# USB.net
KiCad netlist of a schematic drawn in Altium Designer
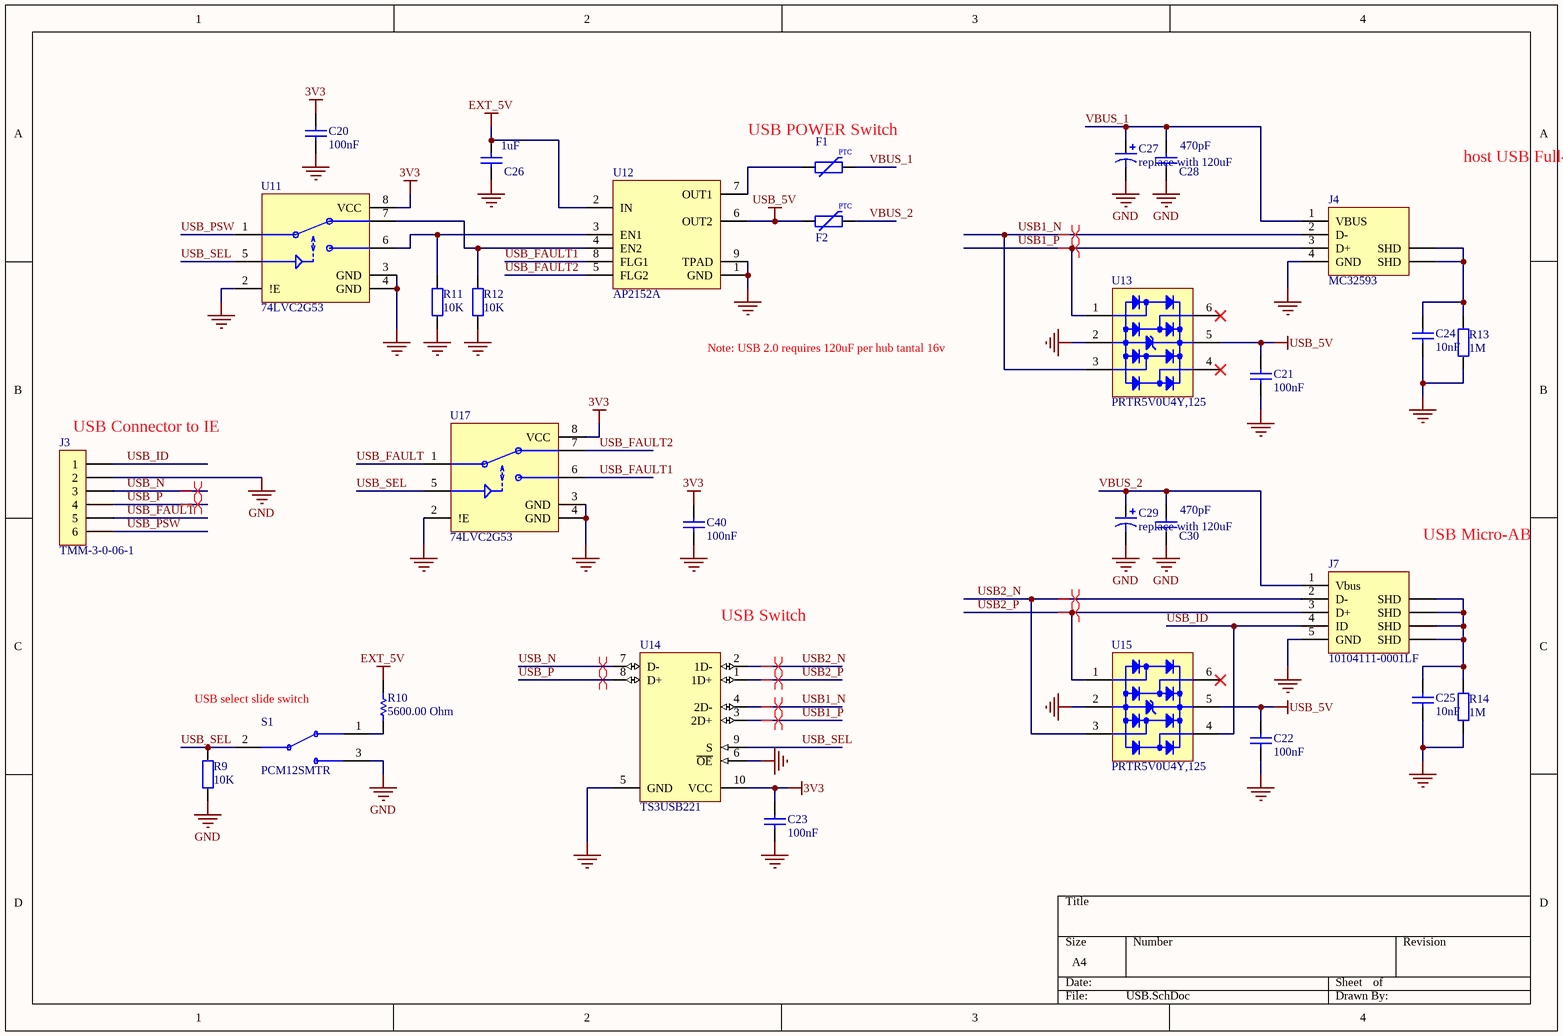
[diagram p0: USB.SchDoc]

(export (version "E")
  (design (tool "Eeschema 10.0.6"))
  (components
    (comp (ref "C20")
      (value "100nF")
      (footprint "CAPC0402(1005)60_L")
      (description "CAP 100nF 10V ±5% 0402 (1005 Metric) Thickness 0.6mm SMD")
      (fields (field (name "TOLERANCE") "Â±5%") (field (name "Comment") "CAP 100nF 10V 0402(1005)"))
      (libsource (lib "Altium Content Vault") (part "CMP-1034-02064-1"))
    )
    (comp (ref "C21")
      (value "100nF")
      (footprint "CAPC0402(1005)60_L")
      (description "CAP 100nF 10V ±5% 0402 (1005 Metric) Thickness 0.6mm SMD")
      (fields (field (name "TOLERANCE") "Â±5%") (field (name "Comment") "CAP 100nF 10V 0402(1005)"))
      (libsource (lib "Altium Content Vault") (part "CMP-1034-02064-1"))
    )
    (comp (ref "C22")
      (value "100nF")
      (footprint "CAPC0402(1005)60_L")
      (description "CAP 100nF 10V ±5% 0402 (1005 Metric) Thickness 0.6mm SMD")
      (fields (field (name "TOLERANCE") "Â±5%") (field (name "Comment") "CAP 100nF 10V 0402(1005)"))
      (libsource (lib "Altium Content Vault") (part "CMP-1034-02064-1"))
    )
    (comp (ref "C23")
      (value "100nF")
      (footprint "CAPC0402(1005)60_L")
      (description "CAP 100nF 10V ±5% 0402 (1005 Metric) Thickness 0.6mm SMD")
      (fields (field (name "TOLERANCE") "Â±5%") (field (name "Comment") "CAP 100nF 10V 0402(1005)"))
      (libsource (lib "Altium Content Vault") (part "CMP-1034-02064-1"))
    )
    (comp (ref "C24")
      (value "10nF")
      (footprint "CAPC0402(1005)60_N")
      (description "CAP 10nF 50V ±10% 0402 (1005 Metric) Thickness 0.6mm SMD")
      (fields (field (name "TOLERANCE") "±10%") (field (name "Comment") "CAP 10nF 50V 0402(1005)"))
      (libsource (lib "Altium Content Vault") (part "CMP-1034-01886-1"))
    )
    (comp (ref "C25")
      (value "10nF")
      (footprint "CAPC0402(1005)60_N")
      (description "CAP 10nF 50V ±10% 0402 (1005 Metric) Thickness 0.6mm SMD")
      (fields (field (name "TOLERANCE") "±10%") (field (name "Comment") "CAP 10nF 50V 0402(1005)"))
      (libsource (lib "Altium Content Vault") (part "CMP-1034-01886-1"))
    )
    (comp (ref "C26")
      (value "1uF")
      (footprint "CAPC0603(1608)100_N")
      (description "CAP 2.2uF 16V ±20% 0603 (1608 Metric) Thickness 1mm SMD")
      (fields (field (name "TOLERANCE") "±20%") (field (name "Comment") "CAP 2.2uF 16V 0603(1608)"))
      (libsource (lib "Altium Content Vault") (part "CMP-1035-02765-1"))
    )
    (comp (ref "C27")
      (value "replace with 120uF")
      (footprint "AVX-CAPC3528_V")
      (description "Capacitor, Tantalum, 10uF 10% 20V MCCT-B (3528)")
      (fields (field (name "PARTNUMBER") "TAJB106K020R") (field (name "MANUFACTURER") "AVX"))
      (libsource (lib "Altium Content Vault") (part "CMP-0279-00001-1"))
    )
    (comp (ref "C28")
      (value "470pF")
      (footprint "CAPC0603(1608)100_M")
      (description "CAP 470pF 16V ±1% 0603 (1608 Metric) Thickness 1mm SMD")
      (fields (field (name "TOLERANCE") "Â±1%") (field (name "Comment") "CAP 470pF 16V 0603(1608)"))
      (libsource (lib "Altium Content Vault") (part "CMP-1035-01663-1"))
    )
    (comp (ref "C29")
      (value "replace with 120uF")
      (footprint "AVX-CAPC3528_V")
      (description "Capacitor, Tantalum, 10uF 10% 20V MCCT-B (3528)")
      (fields (field (name "PARTNUMBER") "TAJB106K020R") (field (name "MANUFACTURER") "AVX"))
      (libsource (lib "Altium Content Vault") (part "CMP-0279-00001-1"))
    )
    (comp (ref "C30")
      (value "470pF")
      (footprint "CAPC0603(1608)100_M")
      (description "CAP 470pF 16V ±1% 0603 (1608 Metric) Thickness 1mm SMD")
      (fields (field (name "TOLERANCE") "Â±1%") (field (name "Comment") "CAP 470pF 16V 0603(1608)"))
      (libsource (lib "Altium Content Vault") (part "CMP-1035-01663-1"))
    )
    (comp (ref "C40")
      (value "100nF")
      (footprint "CAPC0402(1005)60_L")
      (description "CAP 100nF 10V ±5% 0402 (1005 Metric) Thickness 0.6mm SMD")
      (fields (field (name "TOLERANCE") "Â±5%") (field (name "Comment") "CAP 100nF 10V 0402(1005)"))
      (libsource (lib "Altium Content Vault") (part "CMP-1034-02064-1"))
    )
    (comp (ref "F1")
      (value "MF-PSMF050X-2")
      (footprint "RESC0805(2012)_L")
      (description "PTC Resettable Fuse")
      (fields (field (name "MANUFACTURER") "Bourns"))
      (libsource (lib "MF-PSMF050X-2") (part "MF-PSMF050X-2"))
    )
    (comp (ref "F2")
      (value "MF-PSMF050X-2")
      (footprint "RESC0805(2012)_L")
      (description "PTC Resettable Fuse")
      (libsource (lib "MF-PSMF050X-2") (part "MF-PSMF050X-2"))
    )
    (comp (ref "J3")
      (value "TMM-3-0-06-1")
      (footprint "Micro-Match_6pin")
      (description "Micro-Match male 6 pin  Through Hole Vertical, Pitch 1.27mm")
      (fields (field (name "MANUFACTURER") "AMPHENOL"))
      (libsource (lib "TMM-3-0-06-1") (part "TMM-3-0-06-1"))
    )
    (comp (ref "J4")
      (value "MC32593")
      (footprint "MC32593")
      (description "USB, Type A, Right Angle, THT")
      (fields (field (name "MANUFACTURER") "MULTICOMP"))
      (libsource (lib "MC32593") (part "MC32593"))
    )
    (comp (ref "J7")
      (value "10104111-0001LF")
      (footprint "10104111-0001LF")
      (description "Micro USB 2.0, Type AB, Bottom Mount, SMT, Right Angle")
      (libsource (lib "10104111-0001LF") (part "10104111-0001LF"))
    )
    (comp (ref "R9")
      (value "10K")
      (footprint "RESC0402(1005)_L")
      (description "10K 0.063W 1% 0402 (1005 Metric)  SMD")
      (fields (field (name "POWER") "0.063W") (field (name "TOLERANCE") "1%"))
      (libsource (lib "RES0402(1005)") (part "10K 0402(1005)_1"))
    )
    (comp (ref "R10")
      (value "5600.00 Ohm")
      (footprint "RESC0402(1005)_L")
      (description "5K6 0.063W 5% 0402 (1005 Metric)  SMD")
      (fields (field (name "TOLERANCE") "5 %") (field (name "POWER") "0.063 W"))
      (libsource (lib "Altium Content Vault") (part "CMP-1011-00092-1"))
    )
    (comp (ref "R11")
      (value "10K")
      (footprint "RESC0402(1005)_N")
      (description "10K 0.063W 1% 0402 (1005 Metric)  SMD")
      (fields (field (name "POWER") "0.063W") (field (name "TOLERANCE") "1%"))
      (libsource (lib "RES0402(1005)") (part "10K 0402(1005)_1"))
    )
    (comp (ref "R12")
      (value "10K")
      (footprint "RESC0402(1005)_N")
      (description "10K 0.063W 1% 0402 (1005 Metric)  SMD")
      (fields (field (name "POWER") "0.063W") (field (name "TOLERANCE") "1%"))
      (libsource (lib "RES0402(1005)") (part "10K 0402(1005)_1"))
    )
    (comp (ref "R13")
      (value "1M")
      (footprint "RESC0402(1005)_L")
      (description "1M  0.063W 1% 0402 (1005 Metric)  SMD")
      (fields (field (name "POWER") "0.063W") (field (name "TOLERANCE") "1%"))
      (libsource (lib "RES0402(1005)") (part "1M 0402(1005)"))
    )
    (comp (ref "R14")
      (value "1M")
      (footprint "RESC0402(1005)_L")
      (description "1M  0.063W 1% 0402 (1005 Metric)  SMD")
      (fields (field (name "POWER") "0.063W") (field (name "TOLERANCE") "1%"))
      (libsource (lib "RES0402(1005)") (part "1M 0402(1005)"))
    )
    (comp (ref "S1")
      (value "PCM12SMTR")
      (footprint "PCM12SMTR switch footprint")
      (description "slide switch")
      (fields (field (name "MANUFACTURER") "C & K COMPONENTS"))
      (libsource (lib "PCM12SMTR") (part "PCM12SMTR"))
    )
    (comp (ref "U11")
      (value "74LVC2G53")
      (footprint "VSSOP8_SOT765-1")
      (libsource (lib "74LVC2G53") (part "74LVC2G53"))
    )
    (comp (ref "U12")
      (value "AP2152A")
      (footprint "SOP127P600-8N")
      (libsource (lib "AP2152A") (part "AP2152A"))
    )
    (comp (ref "U13")
      (value "PRTR5V0U4Y,125")
      (footprint "SOT363_L")
      (fields (field (name "MANUFACTURER") "NXP"))
      (libsource (lib "PRTR5V0U4Y") (part "PRTR5V0U4Y,125"))
    )
    (comp (ref "U14")
      (value "TS3USB221")
      (footprint "RSE10")
      (fields (field (name "PARTNUMBER") "TS3USB221ARSER") (field (name "MANUFACTURER") "Texas Instruments"))
      (libsource (lib "Altium Content Vault") (part "CMP-0309-00017-1"))
    )
    (comp (ref "U15")
      (value "PRTR5V0U4Y,125")
      (footprint "SOT363_L")
      (fields (field (name "MANUFACTURER") "NXP"))
      (libsource (lib "PRTR5V0U4Y") (part "PRTR5V0U4Y,125"))
    )
    (comp (ref "U17")
      (value "74LVC2G53")
      (footprint "VSSOP8_SOT765-1")
      (libsource (lib "74LVC2G53") (part "74LVC2G53"))
    )
  )
  (nets
    (net (code "1") (name "/USB1_N") (class "Default")
      (node (ref "J4") (pin "2") (pinfunction "D-_2") (pintype "passive"))
      (node (ref "U13") (pin "3") (pinfunction "3_3") (pintype "passive"))
      (node (ref "U14") (pin "4") (pinfunction "2D-_4") (pintype "bidirectional"))
    )
    (net (code "2") (name "/USB1_P") (class "Default")
      (node (ref "J4") (pin "3") (pinfunction "D+_3") (pintype "passive"))
      (node (ref "U13") (pin "1") (pinfunction "1_1") (pintype "passive"))
      (node (ref "U14") (pin "3") (pinfunction "2D+_3") (pintype "bidirectional"))
    )
    (net (code "3") (name "/USB2_N") (class "Default")
      (node (ref "J7") (pin "2") (pinfunction "D-_2") (pintype "passive"))
      (node (ref "U14") (pin "2") (pinfunction "1D-_2") (pintype "bidirectional"))
      (node (ref "U15") (pin "3") (pinfunction "3_3") (pintype "passive"))
    )
    (net (code "4") (name "/USB2_P") (class "Default")
      (node (ref "J7") (pin "3") (pinfunction "D+_3") (pintype "passive"))
      (node (ref "U14") (pin "1") (pinfunction "1D+_1") (pintype "bidirectional"))
      (node (ref "U15") (pin "1") (pinfunction "1_1") (pintype "passive"))
    )
    (net (code "5") (name "/USB_FAULT") (class "Default")
      (node (ref "J3") (pin "5") (pinfunction "5_5") (pintype "passive"))
      (node (ref "U17") (pin "1") (pinfunction "Z_1") (pintype "passive"))
    )
    (net (code "6") (name "/USB_FAULT1") (class "Default")
      (node (ref "U12") (pin "8") (pinfunction "FLG1_8") (pintype "passive"))
      (node (ref "U17") (pin "6") (pinfunction "Y1_6") (pintype "passive"))
    )
    (net (code "7") (name "/USB_FAULT2") (class "Default")
      (node (ref "U12") (pin "5") (pinfunction "FLG2_5") (pintype "passive"))
      (node (ref "U17") (pin "7") (pinfunction "Y0_7") (pintype "passive"))
    )
    (net (code "8") (name "/USB_ID") (class "Default")
      (node (ref "J3") (pin "1") (pinfunction "1_1") (pintype "passive"))
      (node (ref "J7") (pin "4") (pinfunction "ID_4") (pintype "passive"))
      (node (ref "U15") (pin "4") (pinfunction "4_4") (pintype "passive"))
    )
    (net (code "9") (name "/USB_N") (class "Default")
      (node (ref "J3") (pin "3") (pinfunction "3_3") (pintype "passive"))
      (node (ref "U14") (pin "7") (pinfunction "D-_7") (pintype "bidirectional"))
    )
    (net (code "10") (name "/USB_P") (class "Default")
      (node (ref "J3") (pin "4") (pinfunction "4_4") (pintype "passive"))
      (node (ref "U14") (pin "8") (pinfunction "D+_8") (pintype "bidirectional"))
    )
    (net (code "11") (name "/USB_PSW") (class "Default")
      (node (ref "J3") (pin "6") (pinfunction "6_6") (pintype "passive"))
      (node (ref "U11") (pin "1") (pinfunction "Z_1") (pintype "passive"))
    )
    (net (code "12") (name "/USB_SEL") (class "Default")
      (node (ref "R9") (pin "2") (pinfunction "2_2") (pintype "passive"))
      (node (ref "S1") (pin "2") (pinfunction "NO1_2") (pintype "passive"))
      (node (ref "U11") (pin "5") (pinfunction "S_5") (pintype "passive"))
      (node (ref "U14") (pin "9") (pinfunction "S_9") (pintype "input"))
      (node (ref "U17") (pin "5") (pinfunction "S_5") (pintype "passive"))
    )
    (net (code "13") (name "/VBUS_1") (class "Default")
      (node (ref "C27") (pin "1") (pinfunction "1_1") (pintype "passive"))
      (node (ref "C28") (pin "2") (pinfunction "2_2") (pintype "passive"))
      (node (ref "F1") (pin "2") (pinfunction "2_2") (pintype "passive"))
      (node (ref "J4") (pin "1") (pinfunction "VBUS_1") (pintype "passive"))
    )
    (net (code "14") (name "/VBUS_2") (class "Default")
      (node (ref "C29") (pin "1") (pinfunction "1_1") (pintype "passive"))
      (node (ref "C30") (pin "2") (pinfunction "2_2") (pintype "passive"))
      (node (ref "F2") (pin "2") (pinfunction "2_2") (pintype "passive"))
      (node (ref "J7") (pin "1") (pinfunction "Vbus_1") (pintype "passive"))
    )
    (net (code "15") (name "3V3") (class "Default")
      (node (ref "C20") (pin "2") (pinfunction "2_2") (pintype "passive"))
      (node (ref "C23") (pin "2") (pinfunction "2_2") (pintype "passive"))
      (node (ref "C40") (pin "2") (pinfunction "2_2") (pintype "passive"))
      (node (ref "U11") (pin "8") (pinfunction "VCC_8") (pintype "passive"))
      (node (ref "U14") (pin "10") (pinfunction "VCC_10") (pintype "power_in"))
      (node (ref "U17") (pin "8") (pinfunction "VCC_8") (pintype "passive"))
    )
    (net (code "16") (name "EXT_5V") (class "Default")
      (node (ref "C26") (pin "2") (pinfunction "2_2") (pintype "passive"))
      (node (ref "R10") (pin "2") (pinfunction "2_2") (pintype "passive"))
      (node (ref "U12") (pin "2") (pinfunction "IN_2") (pintype "passive"))
    )
    (net (code "17") (name "GND") (class "Default")
      (node (ref "C20") (pin "1") (pinfunction "1_1") (pintype "passive"))
      (node (ref "C21") (pin "1") (pinfunction "1_1") (pintype "passive"))
      (node (ref "C22") (pin "1") (pinfunction "1_1") (pintype "passive"))
      (node (ref "C23") (pin "1") (pinfunction "1_1") (pintype "passive"))
      (node (ref "C24") (pin "1") (pinfunction "1_1") (pintype "passive"))
      (node (ref "C25") (pin "1") (pinfunction "1_1") (pintype "passive"))
      (node (ref "C26") (pin "1") (pinfunction "1_1") (pintype "passive"))
      (node (ref "C27") (pin "2") (pinfunction "2_2") (pintype "passive"))
      (node (ref "C28") (pin "1") (pinfunction "1_1") (pintype "passive"))
      (node (ref "C29") (pin "2") (pinfunction "2_2") (pintype "passive"))
      (node (ref "C30") (pin "1") (pinfunction "1_1") (pintype "passive"))
      (node (ref "C40") (pin "1") (pinfunction "1_1") (pintype "passive"))
      (node (ref "J3") (pin "2") (pinfunction "2_2") (pintype "passive"))
      (node (ref "J4") (pin "4") (pinfunction "GND_4") (pintype "passive"))
      (node (ref "J7") (pin "5") (pinfunction "GND_5") (pintype "passive"))
      (node (ref "R11") (pin "1") (pinfunction "1_1") (pintype "passive"))
      (node (ref "R12") (pin "1") (pinfunction "1_1") (pintype "passive"))
      (node (ref "R13") (pin "1") (pinfunction "1_1") (pintype "passive"))
      (node (ref "R14") (pin "1") (pinfunction "1_1") (pintype "passive"))
      (node (ref "R9") (pin "1") (pinfunction "1_1") (pintype "passive"))
      (node (ref "S1") (pin "3") (pinfunction "NC2_3") (pintype "passive"))
      (node (ref "U11") (pin "2") (pinfunction "!E_2") (pintype "passive"))
      (node (ref "U11") (pin "3") (pinfunction "GND_3") (pintype "passive"))
      (node (ref "U11") (pin "4") (pinfunction "GND_4") (pintype "passive"))
      (node (ref "U12") (pin "1") (pinfunction "GND_1") (pintype "passive"))
      (node (ref "U12") (pin "9") (pinfunction "TPAD_9") (pintype "passive"))
      (node (ref "U13") (pin "2") (pinfunction "2_2") (pintype "passive"))
      (node (ref "U14") (pin "5") (pinfunction "GND_5") (pintype "power_in"))
      (node (ref "U14") (pin "6") (pinfunction "~{OE}_6") (pintype "input"))
      (node (ref "U15") (pin "2") (pinfunction "2_2") (pintype "passive"))
      (node (ref "U17") (pin "2") (pinfunction "!E_2") (pintype "passive"))
      (node (ref "U17") (pin "3") (pinfunction "GND_3") (pintype "passive"))
      (node (ref "U17") (pin "4") (pinfunction "GND_4") (pintype "passive"))
    )
    (net (code "18") (name "Net-(C24-Pad2)") (class "Default")
      (node (ref "C24") (pin "2") (pinfunction "2_2") (pintype "passive"))
      (node (ref "J4") (pin "5") (pinfunction "SHD_5") (pintype "passive"))
      (node (ref "J4") (pin "6") (pinfunction "SHD_6") (pintype "passive"))
      (node (ref "R13") (pin "2") (pinfunction "2_2") (pintype "passive"))
    )
    (net (code "19") (name "Net-(C25-Pad2)") (class "Default")
      (node (ref "C25") (pin "2") (pinfunction "2_2") (pintype "passive"))
      (node (ref "J7") (pin "6") (pinfunction "SHD_6") (pintype "passive"))
      (node (ref "J7") (pin "7") (pinfunction "SHD_7") (pintype "passive"))
      (node (ref "J7") (pin "8") (pinfunction "SHD_8") (pintype "passive"))
      (node (ref "J7") (pin "9") (pinfunction "SHD_9") (pintype "passive"))
      (node (ref "R14") (pin "2") (pinfunction "2_2") (pintype "passive"))
    )
    (net (code "20") (name "Net-(S1-NC1)") (class "Default")
      (node (ref "R10") (pin "1") (pinfunction "1_1") (pintype "passive"))
      (node (ref "S1") (pin "1") (pinfunction "NC1_1") (pintype "passive"))
    )
    (net (code "21") (name "Net-(U11-Y0)") (class "Default")
      (node (ref "R12") (pin "2") (pinfunction "2_2") (pintype "passive"))
      (node (ref "U11") (pin "7") (pinfunction "Y0_7") (pintype "passive"))
      (node (ref "U12") (pin "4") (pinfunction "EN2_4") (pintype "passive"))
    )
    (net (code "22") (name "Net-(U11-Y1)") (class "Default")
      (node (ref "R11") (pin "2") (pinfunction "2_2") (pintype "passive"))
      (node (ref "U11") (pin "6") (pinfunction "Y1_6") (pintype "passive"))
      (node (ref "U12") (pin "3") (pinfunction "EN1_3") (pintype "passive"))
    )
    (net (code "23") (name "Net-(U12-OUT1)") (class "Default")
      (node (ref "F1") (pin "1") (pinfunction "1_1") (pintype "passive"))
      (node (ref "U12") (pin "7") (pinfunction "OUT1_7") (pintype "passive"))
    )
    (net (code "24") (name "USB_5V") (class "Default")
      (node (ref "C21") (pin "2") (pinfunction "2_2") (pintype "passive"))
      (node (ref "C22") (pin "2") (pinfunction "2_2") (pintype "passive"))
      (node (ref "F2") (pin "1") (pinfunction "1_1") (pintype "passive"))
      (node (ref "U12") (pin "6") (pinfunction "OUT2_6") (pintype "passive"))
      (node (ref "U13") (pin "5") (pinfunction "5_5") (pintype "passive"))
      (node (ref "U15") (pin "5") (pinfunction "5_5") (pintype "passive"))
    )
    (net (code "25") (name "unconnected-(U13-Pad4)") (class "Default")
      (node (ref "U13") (pin "4") (pinfunction "4_4") (pintype "passive+no_connect"))
    )
    (net (code "26") (name "unconnected-(U13-Pad6)") (class "Default")
      (node (ref "U13") (pin "6") (pinfunction "6_6") (pintype "passive+no_connect"))
    )
    (net (code "27") (name "unconnected-(U15-Pad6)") (class "Default")
      (node (ref "U15") (pin "6") (pinfunction "6_6") (pintype "passive+no_connect"))
    )
  )
)
